# myhalf.net
KiCad netlist of a schematic drawn in EAGLE
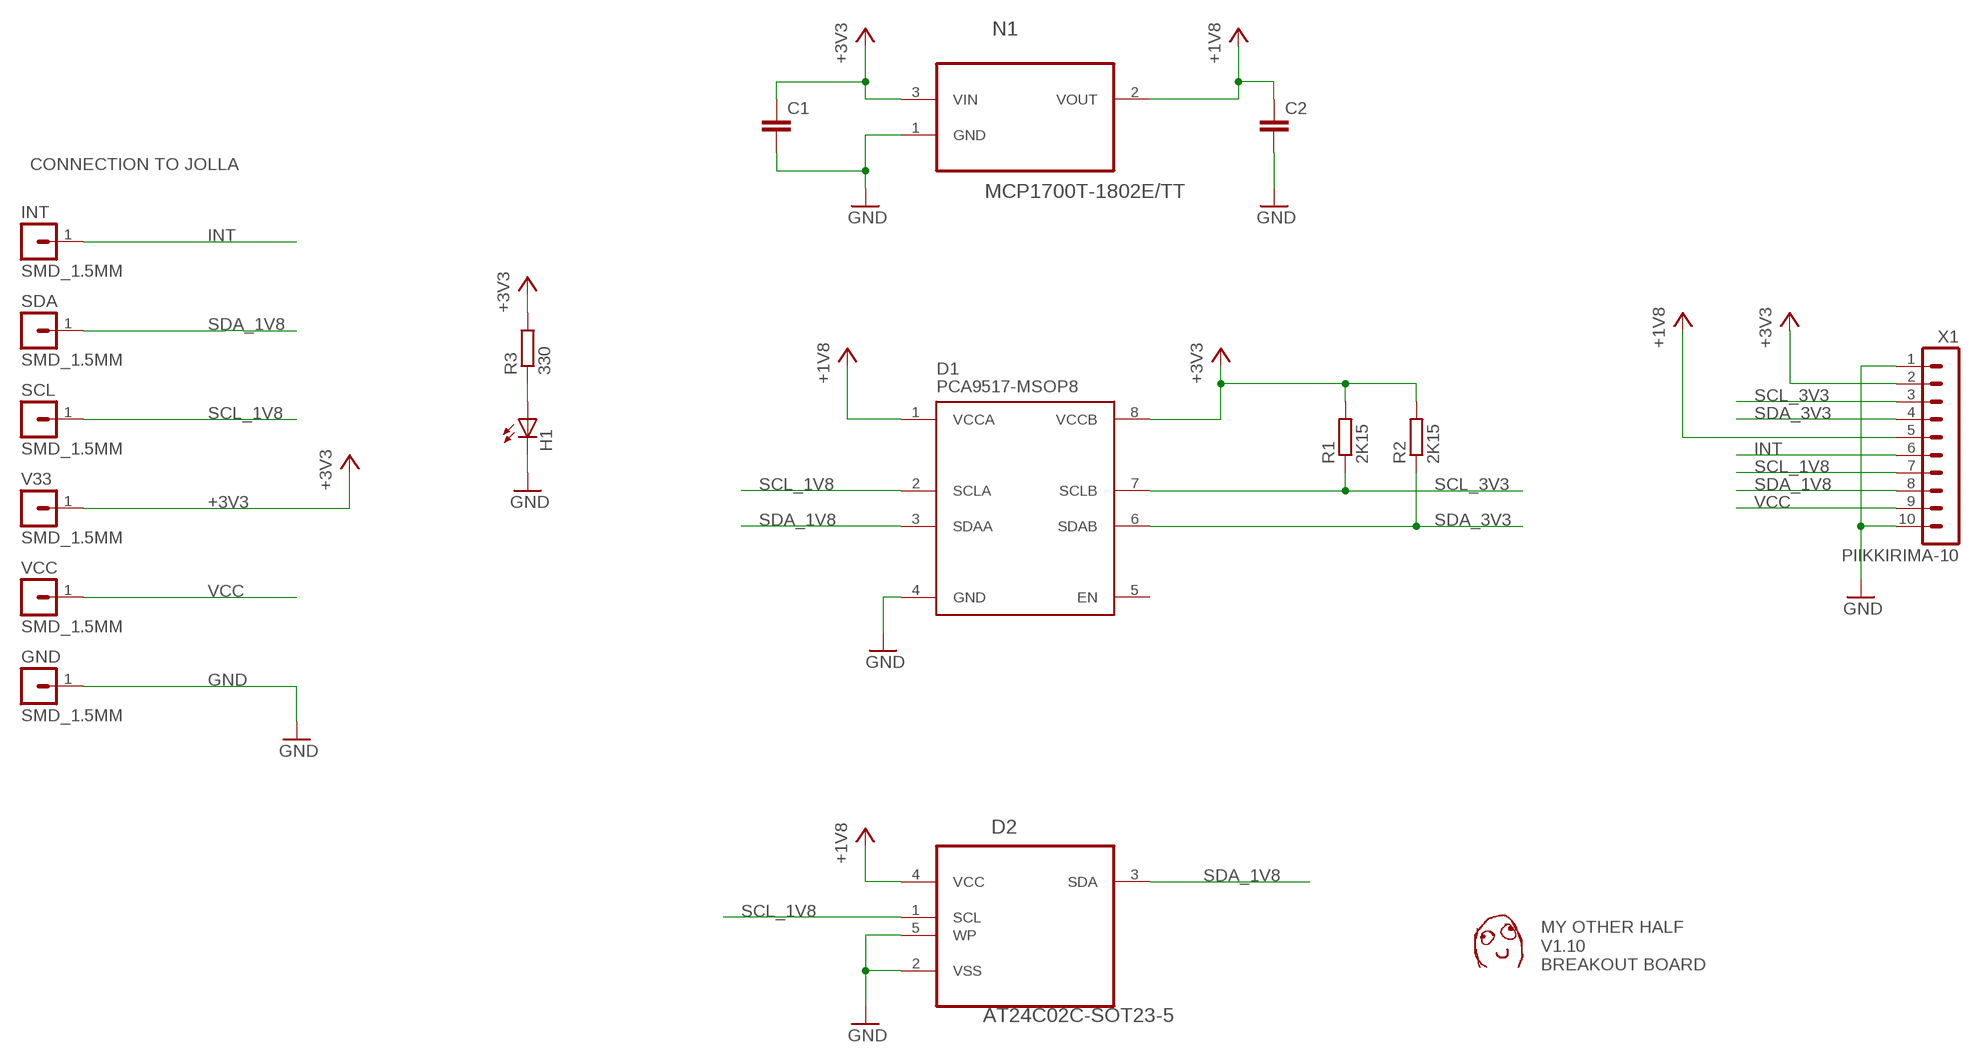
[diagram p0: schematic, sheet 1]

(export (version "E")
  (design (tool "Eeschema 10.0.6"))
  (components
    (comp (ref "C1")
      (value "C-EUC0603")
      (footprint "eagle-import:C0603")
      (libsource (lib "eagle-import") (part "C-EUC0603"))
    )
    (comp (ref "C2")
      (value "C-EUC0603")
      (footprint "eagle-import:C0603")
      (libsource (lib "eagle-import") (part "C-EUC0603"))
    )
    (comp (ref "D1")
      (value "PCA9517-MSOP8")
      (footprint "eagle-import:SOP65P490X110-8N")
      (libsource (lib "eagle-import") (part "PCA9517"))
    )
    (comp (ref "D2")
      (value "AT24C02C-SOT23-5")
      (footprint "eagle-import:SOT95P280X145-5N")
      (fields (field (name "MPN") "24LC01BT-I/OT"))
      (libsource (lib "eagle-import") (part "24LC01BT-I/OT"))
    )
    (comp (ref "GND")
      (value "SMD_1.5MM")
      (footprint "eagle-import:SMD_ROUND_1.5MM")
      (libsource (lib "eagle-import") (part "SMD_1.5MM"))
    )
    (comp (ref "H1")
      (value "LEDCHIP-LED0603")
      (footprint "eagle-import:CHIP-LED0603")
      (libsource (lib "eagle-import") (part "LEDCHIP-LED0603"))
    )
    (comp (ref "INT")
      (value "SMD_1.5MM")
      (footprint "eagle-import:SMD_ROUND_1.5MM")
      (libsource (lib "eagle-import") (part "SMD_1.5MM"))
    )
    (comp (ref "N1")
      (value "MCP1700T-1802E/TT")
      (footprint "eagle-import:SOT95P237X112-3N")
      (libsource (lib "eagle-import") (part "MCP1700T-1802E/TT"))
    )
    (comp (ref "R1")
      (value "2K15")
      (footprint "eagle-import:R0603")
      (libsource (lib "eagle-import") (part "R-EU_R0603"))
    )
    (comp (ref "R2")
      (value "2K15")
      (footprint "eagle-import:R0603")
      (libsource (lib "eagle-import") (part "R-EU_R0603"))
    )
    (comp (ref "R3")
      (value "330")
      (footprint "eagle-import:R0603")
      (libsource (lib "eagle-import") (part "R-EU_R0603"))
    )
    (comp (ref "SCL")
      (value "SMD_1.5MM")
      (footprint "eagle-import:SMD_ROUND_1.5MM")
      (libsource (lib "eagle-import") (part "SMD_1.5MM"))
    )
    (comp (ref "SDA")
      (value "SMD_1.5MM")
      (footprint "eagle-import:SMD_ROUND_1.5MM")
      (libsource (lib "eagle-import") (part "SMD_1.5MM"))
    )
    (comp (ref "U$1")
      (value "DAFUG")
      (footprint "eagle-import:DAFUG")
      (libsource (lib "eagle-import") (part "DAFUG"))
    )
    (comp (ref "V33")
      (value "SMD_1.5MM")
      (footprint "eagle-import:SMD_ROUND_1.5MM")
      (libsource (lib "eagle-import") (part "SMD_1.5MM"))
    )
    (comp (ref "VCC")
      (value "SMD_1.5MM")
      (footprint "eagle-import:SMD_ROUND_1.5MM")
      (libsource (lib "eagle-import") (part "SMD_1.5MM"))
    )
    (comp (ref "X1")
      (value "PIIKKIRIMA-10")
      (footprint "eagle-import:PIIKKIRIMA-10")
      (libsource (lib "eagle-import") (part "PIIKKIRIMA-10"))
    )
  )
  (nets
    (net (code "1") (name "+1V8") (class "Default")
      (node (ref "C2") (pin "1") (pinfunction "1_1") (pintype "passive"))
      (node (ref "D1") (pin "1") (pinfunction "VCCA_1") (pintype "bidirectional"))
      (node (ref "D2") (pin "4") (pinfunction "VCC_4") (pintype "power_in"))
      (node (ref "N1") (pin "2") (pinfunction "VOUT_2") (pintype "output"))
      (node (ref "X1") (pin "5") (pinfunction "5_5") (pintype "passive"))
    )
    (net (code "2") (name "+3V3") (class "Default")
      (node (ref "C1") (pin "1") (pinfunction "1_1") (pintype "passive"))
      (node (ref "D1") (pin "8") (pinfunction "VCCB_8") (pintype "bidirectional"))
      (node (ref "N1") (pin "3") (pinfunction "VIN_3") (pintype "input"))
      (node (ref "R1") (pin "2") (pinfunction "2_2") (pintype "passive"))
      (node (ref "R2") (pin "2") (pinfunction "2_2") (pintype "passive"))
      (node (ref "R3") (pin "2") (pinfunction "2_2") (pintype "passive"))
      (node (ref "V33") (pin "1") (pinfunction "1_1") (pintype "passive"))
      (node (ref "X1") (pin "2") (pinfunction "2_2") (pintype "passive"))
    )
    (net (code "3") (name "/INT") (class "Default")
      (node (ref "INT") (pin "1") (pinfunction "1_1") (pintype "passive"))
      (node (ref "X1") (pin "6") (pinfunction "6_6") (pintype "passive"))
    )
    (net (code "4") (name "/SCL_1V8") (class "Default")
      (node (ref "D1") (pin "2") (pinfunction "SCLA_2") (pintype "bidirectional"))
      (node (ref "D2") (pin "1") (pinfunction "SCL_1") (pintype "input"))
      (node (ref "SCL") (pin "1") (pinfunction "1_1") (pintype "passive"))
      (node (ref "X1") (pin "7") (pinfunction "7_7") (pintype "passive"))
    )
    (net (code "5") (name "/SCL_3V3") (class "Default")
      (node (ref "D1") (pin "7") (pinfunction "SCLB_7") (pintype "bidirectional"))
      (node (ref "R1") (pin "1") (pinfunction "1_1") (pintype "passive"))
      (node (ref "X1") (pin "3") (pinfunction "3_3") (pintype "passive"))
    )
    (net (code "6") (name "/SDA_1V8") (class "Default")
      (node (ref "D1") (pin "3") (pinfunction "SDAA_3") (pintype "bidirectional"))
      (node (ref "D2") (pin "3") (pinfunction "SDA_3") (pintype "bidirectional"))
      (node (ref "SDA") (pin "1") (pinfunction "1_1") (pintype "passive"))
      (node (ref "X1") (pin "8") (pinfunction "8_8") (pintype "passive"))
    )
    (net (code "7") (name "/SDA_3V3") (class "Default")
      (node (ref "D1") (pin "6") (pinfunction "SDAB_6") (pintype "bidirectional"))
      (node (ref "R2") (pin "1") (pinfunction "1_1") (pintype "passive"))
      (node (ref "X1") (pin "4") (pinfunction "4_4") (pintype "passive"))
    )
    (net (code "8") (name "/VCC") (class "Default")
      (node (ref "VCC") (pin "1") (pinfunction "1_1") (pintype "passive"))
      (node (ref "X1") (pin "9") (pinfunction "9_9") (pintype "passive"))
    )
    (net (code "9") (name "GND") (class "Default")
      (node (ref "C1") (pin "2") (pinfunction "2_2") (pintype "passive"))
      (node (ref "C2") (pin "2") (pinfunction "2_2") (pintype "passive"))
      (node (ref "D1") (pin "4") (pinfunction "GND_4") (pintype "bidirectional"))
      (node (ref "D2") (pin "2") (pinfunction "VSS_2") (pintype "passive"))
      (node (ref "D2") (pin "5") (pinfunction "WP_5") (pintype "input"))
      (node (ref "GND") (pin "1") (pinfunction "1_1") (pintype "passive"))
      (node (ref "H1") (pin "C") (pinfunction "C_C") (pintype "passive"))
      (node (ref "N1") (pin "1") (pinfunction "GND_1") (pintype "passive"))
      (node (ref "X1") (pin "1") (pinfunction "1_1") (pintype "passive"))
      (node (ref "X1") (pin "10") (pinfunction "10_10") (pintype "passive"))
    )
    (net (code "10") (name "Net-(H1-PadA)") (class "Default")
      (node (ref "H1") (pin "A") (pinfunction "A_A") (pintype "passive"))
      (node (ref "R3") (pin "1") (pinfunction "1_1") (pintype "passive"))
    )
    (net (code "11") (name "unconnected-(D1-EN-Pad5)") (class "Default")
      (node (ref "D1") (pin "5") (pinfunction "EN_5") (pintype "bidirectional"))
    )
  )
)
